# Sheet1.net
KiCad netlist of a schematic drawn in Altium Designer
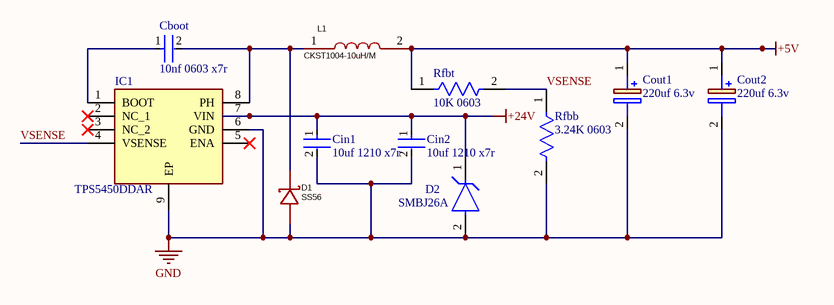
[diagram p0: Sheet1.SchDoc]

(export (version "E")
  (design (tool "Eeschema 10.0.6"))
  (components
    (comp (ref "Cboot")
      (value "10nf 0603 x7r")
      (footprint "FP-C0603C-CF-MFG")
      (description "CAP CER 10000PF 50V X7R 0603")
      (fields (field (name "TOLERANCE") "0.1") (field (name "MANUFACTURER PART NUMBER") "C0603C103K5RACAUTO"))
      (libsource (lib "Altium Content Vault") (part "b4654b650e69147ec39a6b967a45e02"))
    )
    (comp (ref "Cin1")
      (value "10uf 1210 x7r")
      (footprint "FP-C1210C106K5RACTU-MFG")
      (description "CAP CER 10UF 50V X7R 1210")
      (fields (field (name "TOLERANCE") "10%") (field (name "VOLTAGE") "50V"))
      (libsource (lib "Altium Content Vault") (part "11868f565c42a9108669ba33697ecf6"))
    )
    (comp (ref "Cin2")
      (value "10uf 1210 x7r")
      (footprint "FP-C1210C106K5RACTU-MFG")
      (description "CAP CER 10UF 50V X7R 1210")
      (fields (field (name "TOLERANCE") "10%") (field (name "VOLTAGE") "50V"))
      (libsource (lib "Altium Content Vault") (part "11868f565c42a9108669ba33697ecf6"))
    )
    (comp (ref "Cout1")
      (value "220uf 6.3v")
      (footprint "SamacSys:CAPPM3528X210N")
      (description "Capacitor Polarised")
      (fields
        (field (name "MANUFACTURER_PART_NUMBER") "TLJB227M006R0500")
        (field (name "MOUSER PART NUMBER") "581-TLJB227M006R0500")
      )
      (libsource (lib "*") (part "TLJB227M006R0500"))
    )
    (comp (ref "Cout2")
      (value "220uf 6.3v")
      (footprint "SamacSys:CAPPM3528X210N")
      (description "Capacitor Polarised")
      (fields
        (field (name "MANUFACTURER_PART_NUMBER") "TLJB227M006R0500")
        (field (name "MOUSER PART NUMBER") "581-TLJB227M006R0500")
      )
      (libsource (lib "*") (part "TLJB227M006R0500"))
    )
    (comp (ref "D1")
      (value "SS56")
      (footprint "SMC_L7.1-W6.2-LS8.1-R-RD")
      (fields (field (name "MANUFACTURER") "MDD(辰达半导体)") (field (name "MANUFACTURER PART") "SS56C"))
      (libsource (lib "SS56 SMC1_SS56 SMC") (part "SS56C_C24138"))
    )
    (comp (ref "D2")
      (value "SMBJ26A")
      (footprint "FP-SMBJ-MFG")
      (description "42.1V Clamp 14.3A Ipp Tvs Diode Surface Mount DO-214AA (SMBJ)")
      (fields (field (name "MANUFACTURER") "Littelfuse"))
      (libsource (lib "Altium Content Vault") (part "f813f71cba58e380607f5dd3caf9714"))
    )
    (comp (ref "IC1")
      (value "TPS5450DDAR")
      (footprint "SamacSys:SOIC127P600X170-9N")
      (description "Integrated Circuit")
      (fields (field (name "MOUSER PART NUMBER") "595-TPS5450DDAR"))
      (libsource (lib "*") (part "TPS5450DDAR"))
    )
    (comp (ref "L1")
      (value "~")
      (footprint "IND-SMD_L11.6-W10.1")
      (fields
        (field (name "MANUFACTURER") "CENKER(岑科)")
        (field (name "MANUFACTURER PART") "CKST1004-10uH/M")
        (field (name "CKST1004-10UH/M") "CKST1004-10uH/M")
        (field (name "TOLERANCE") "±20%")
      )
      (libsource (lib "CKST1004-10UH_M1_CKST1004-10UH_M") (part "CKST1004-10uH/M"))
    )
    (comp (ref "Rfbb")
      (value "3.24K 0603")
      (footprint "FP-RT0603-MFG")
      (description "RT0603 3.24KΩ 0.1W 25 ppm/°C 0.10%")
      (fields (field (name "TOLERANCE") "0.001"))
      (libsource (lib "Altium Content Vault") (part "1029c3af85768c4190bb7ad29bc67b5"))
    )
    (comp (ref "Rfbt")
      (value "10K 0603")
      (footprint "FP-RC0603-0_55-IPC_C")
      (description "RES 10K OHM 1% 1/10W 0603")
      (fields (field (name "TOLERANCE") "1%"))
      (libsource (lib "Altium Content Vault") (part "1029c3af85768c4190bb7ad29bc67b5"))
    )
  )
  (nets
    (net (code "1") (name "+5V") (class "Default")
      (node (ref "Cout1") (pin "1") (pinfunction "+_1") (pintype "passive"))
      (node (ref "Cout2") (pin "1") (pinfunction "+_1") (pintype "passive"))
      (node (ref "L1") (pin "2") (pinfunction "2_2") (pintype "passive"))
      (node (ref "Rfbt") (pin "1") (pinfunction "1_1") (pintype "passive"))
    )
    (net (code "2") (name "+24V") (class "Default")
      (node (ref "Cin1") (pin "1") (pinfunction "1_1") (pintype "passive"))
      (node (ref "Cin2") (pin "1") (pinfunction "1_1") (pintype "passive"))
      (node (ref "D2") (pin "1") (pinfunction "C_1") (pintype "passive"))
      (node (ref "IC1") (pin "7") (pinfunction "VIN_7") (pintype "passive"))
    )
    (net (code "3") (name "/VSENSE") (class "Default")
      (node (ref "IC1") (pin "4") (pinfunction "VSENSE_4") (pintype "passive"))
      (node (ref "Rfbb") (pin "1") (pinfunction "1_1") (pintype "passive"))
      (node (ref "Rfbt") (pin "2") (pinfunction "2_2") (pintype "passive"))
    )
    (net (code "4") (name "GND") (class "Default")
      (node (ref "Cin1") (pin "2") (pinfunction "2_2") (pintype "passive"))
      (node (ref "Cin2") (pin "2") (pinfunction "2_2") (pintype "passive"))
      (node (ref "Cout1") (pin "2") (pinfunction "-_2") (pintype "passive"))
      (node (ref "Cout2") (pin "2") (pinfunction "-_2") (pintype "passive"))
      (node (ref "D1") (pin "1") (pinfunction "A_1") (pintype "passive"))
      (node (ref "D2") (pin "2") (pinfunction "A_2") (pintype "passive"))
      (node (ref "IC1") (pin "6") (pinfunction "GND_6") (pintype "passive"))
      (node (ref "IC1") (pin "9") (pinfunction "EP_9") (pintype "passive"))
      (node (ref "Rfbb") (pin "2") (pinfunction "2_2") (pintype "passive"))
    )
    (net (code "5") (name "Net-(D1-K)") (class "Default")
      (node (ref "Cboot") (pin "2") (pinfunction "2_2") (pintype "passive"))
      (node (ref "D1") (pin "2") (pinfunction "K_2") (pintype "passive"))
      (node (ref "IC1") (pin "8") (pinfunction "PH_8") (pintype "passive"))
      (node (ref "L1") (pin "1") (pinfunction "1_1") (pintype "passive"))
    )
    (net (code "6") (name "Net-(IC1-BOOT)") (class "Default")
      (node (ref "Cboot") (pin "1") (pinfunction "1_1") (pintype "passive"))
      (node (ref "IC1") (pin "1") (pinfunction "BOOT_1") (pintype "passive"))
    )
    (net (code "7") (name "unconnected-(IC1-ENA-Pad5)") (class "Default")
      (node (ref "IC1") (pin "5") (pinfunction "ENA_5") (pintype "passive+no_connect"))
    )
    (net (code "8") (name "unconnected-(IC1-NC_1-Pad2)") (class "Default")
      (node (ref "IC1") (pin "2") (pinfunction "NC_1_2") (pintype "passive+no_connect"))
    )
    (net (code "9") (name "unconnected-(IC1-NC_2-Pad3)") (class "Default")
      (node (ref "IC1") (pin "3") (pinfunction "NC_2_3") (pintype "passive+no_connect"))
    )
  )
)
